# coba1.net
KiCad netlist of a schematic drawn in EasyEDA Pro
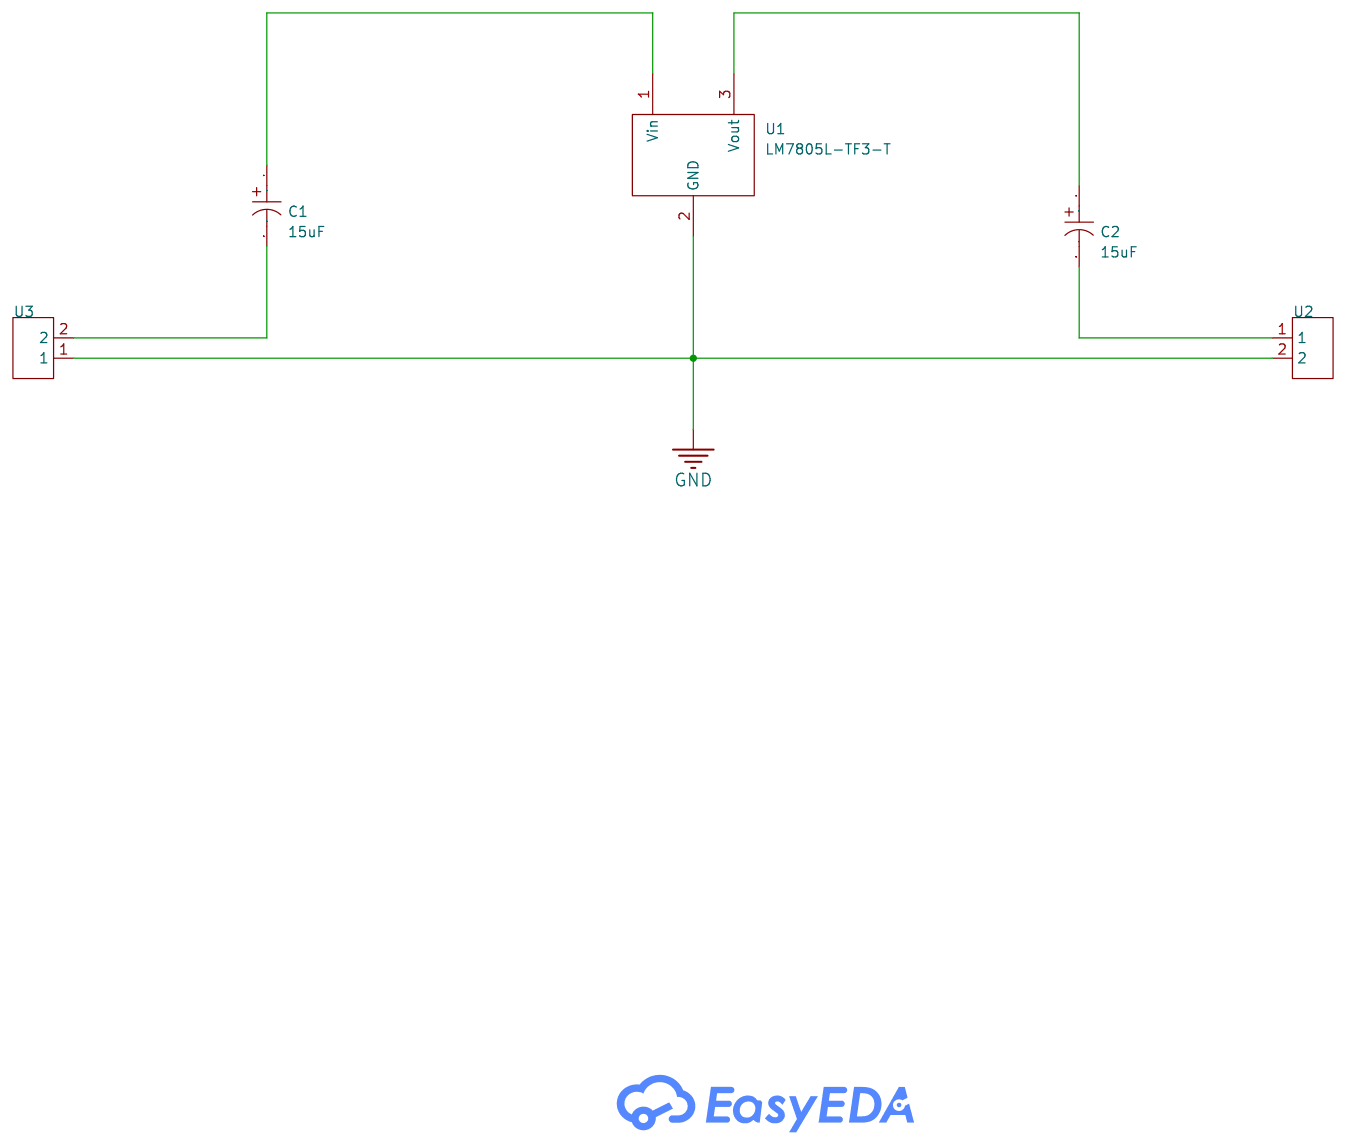
[diagram p0: schematic sheet]

(export (version "E")
  (design (tool "Eeschema 10.0.6"))
  (components
    (comp (ref "C1")
      (value "15uF")
      (footprint "easyedapro:CAP-TH_BD8.3-P3.00-D0.6-FD")
      (libsource (lib "easyedapro") (part "15UF 450V"))
    )
    (comp (ref "C2")
      (value "15uF")
      (footprint "easyedapro:CAP-TH_BD8.3-P3.00-D0.6-FD")
      (libsource (lib "easyedapro") (part "15UF 450V"))
    )
    (comp (ref "U1")
      (value "LM7805L-TF3-T")
      (footprint "easyedapro:TO-220F-3_L10.2-W4.9-P2.54-L")
      (fields (field (name "Manufacturer") "UTC(友顺)"))
      (libsource (lib "easyedapro") (part "LM7805L-TF3-T"))
    )
    (comp (ref "U2")
      (value "TERM BLOCK HDR 2POS VERT 3.81M")
      (footprint "easyedapro:CONN-TH_2P-P3.81_DB2EVC-3.81-2P-WT")
      (libsource (lib "easyedapro") (part "TERM BLOCK HDR 2POS VERT 3.81M"))
    )
    (comp (ref "U3")
      (value "TERM BLOCK HDR 2POS VERT 3.81M")
      (footprint "easyedapro:CONN-TH_2P-P3.81_DB2EVC-3.81-2P-WT")
      (libsource (lib "easyedapro") (part "TERM BLOCK HDR 2POS VERT 3.81M"))
    )
  )
  (nets
    (net (code "1") (name "GND") (class "Default")
      (node (ref "U1") (pin "2") (pinfunction "GND_2") (pintype "input"))
      (node (ref "U2") (pin "2") (pinfunction "2_2") (pintype "unspecified"))
      (node (ref "U3") (pin "1") (pinfunction "1_1") (pintype "unspecified"))
    )
    (net (code "2") (name "Net-(C1-Pad2)") (class "Default")
      (node (ref "C1") (pin "2") (pinfunction "2_2") (pintype "input"))
      (node (ref "U3") (pin "2") (pinfunction "2_2") (pintype "unspecified"))
    )
    (net (code "3") (name "Net-(C2-Pad2)") (class "Default")
      (node (ref "C2") (pin "2") (pinfunction "2_2") (pintype "input"))
      (node (ref "U2") (pin "1") (pinfunction "1_1") (pintype "unspecified"))
    )
    (net (code "4") (name "Net-(U1-Vin)") (class "Default")
      (node (ref "C1") (pin "1") (pinfunction "1_1") (pintype "input"))
      (node (ref "U1") (pin "1") (pinfunction "Vin_1") (pintype "input"))
    )
    (net (code "5") (name "Net-(U1-Vout)") (class "Default")
      (node (ref "C2") (pin "1") (pinfunction "1_1") (pintype "input"))
      (node (ref "U1") (pin "3") (pinfunction "Vout_3") (pintype "input"))
    )
  )
)
